# OLD_eps_bb1.net
KiCad netlist of a schematic drawn in Altium Designer
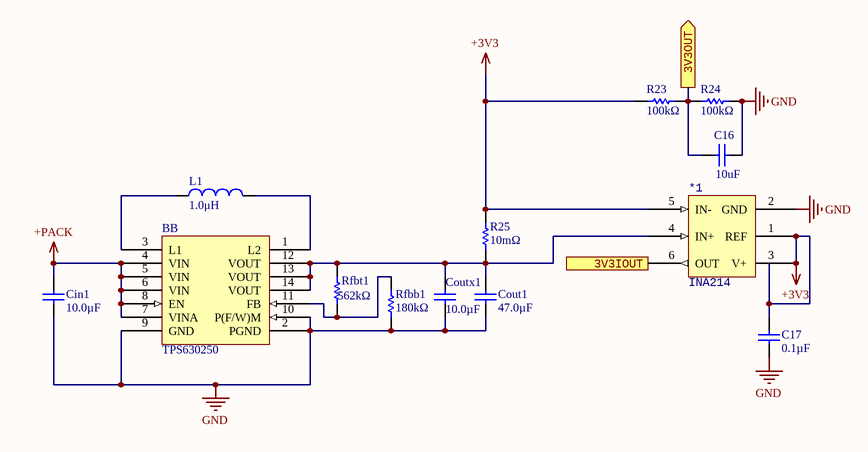
[diagram p0: OLD_eps_bb1.SchDoc]

(export (version "E")
  (design (tool "Eeschema 10.0.6"))
  (components
    (comp (ref "*1")
      (value "INA214")
      (footprint "SOT65P210X110-6N")
      (description "Current monitor")
      (libsource (lib "EPS") (part "INA214"))
    )
    (comp (ref "BB")
      (value "TPS630250")
      (footprint "RNC0014A")
      (description "Buck-boost converter")
      (libsource (lib "heron-general") (part "TPS630250"))
    )
    (comp (ref "C16")
      (value "10uF")
      (footprint "1608[0603]")
      (description "Capacitor")
      (fields (field (name "PUBLISHER") "Altium Limited"))
      (libsource (lib "Miscellaneous Devices") (part "Cap"))
    )
    (comp (ref "C17")
      (value "0.1µF")
      (footprint "1608[0603]")
      (description "Capacitor (Semiconductor SIM Model)")
      (fields (field (name "PUBLISHER") "Altium Limited"))
      (libsource (lib "Miscellaneous Devices") (part "Cap Semi"))
    )
    (comp (ref "Cin1")
      (value "10.0µF")
      (footprint "1608[0603]")
      (description "Capacitor")
      (fields (field (name "PUBLISHER") "Altium Limited"))
      (libsource (lib "Miscellaneous Devices") (part "Cap"))
    )
    (comp (ref "Cout1")
      (value "47.0µF")
      (footprint "1608[0603]")
      (description "Capacitor")
      (fields (field (name "PUBLISHER") "Altium Limited"))
      (libsource (lib "Miscellaneous Devices") (part "Cap"))
    )
    (comp (ref "Coutx1")
      (value "10.0µF")
      (footprint "1608[0603]")
      (description "Capacitor")
      (fields (field (name "PUBLISHER") "Altium Limited"))
      (libsource (lib "Miscellaneous Devices") (part "Cap"))
    )
    (comp (ref "L1")
      (value "1.0μH")
      (footprint "1608[0603]")
      (description "Inductor")
      (fields (field (name "PUBLISHER") "Altium Limited"))
      (libsource (lib "Miscellaneous Devices") (part "Inductor"))
    )
    (comp (ref "R23")
      (value "100kΩ")
      (footprint "1608[0603]")
      (description "Resistor")
      (fields (field (name "PUBLISHER") "Altium Limited"))
      (libsource (lib "Miscellaneous Devices") (part "Res1"))
    )
    (comp (ref "R24")
      (value "100kΩ")
      (footprint "1608[0603]")
      (description "Resistor")
      (fields (field (name "PUBLISHER") "Altium Limited"))
      (libsource (lib "Miscellaneous Devices") (part "Res1"))
    )
    (comp (ref "R25")
      (value "10mΩ")
      (footprint "1608[0603]")
      (description "Resistor")
      (fields (field (name "PUBLISHER") "Altium Limited"))
      (libsource (lib "Miscellaneous Devices") (part "Res1"))
    )
    (comp (ref "Rfbb1")
      (value "180kΩ")
      (footprint "1608[0603]")
      (description "Resistor")
      (fields (field (name "PUBLISHER") "Altium Limited"))
      (libsource (lib "Miscellaneous Devices") (part "Res1"))
    )
    (comp (ref "Rfbt1")
      (value "562kΩ")
      (footprint "1608[0603]")
      (description "Resistor")
      (fields (field (name "PUBLISHER") "Altium Limited"))
      (libsource (lib "Miscellaneous Devices") (part "Res1"))
    )
  )
  (nets
    (net (code "1") (name "+3V3") (class "Default")
      (node (ref "*1") (pin "1") (pinfunction "REF_1") (pintype "passive"))
      (node (ref "*1") (pin "3") (pinfunction "V+_3") (pintype "power_in"))
      (node (ref "*1") (pin "5") (pinfunction "IN-_5") (pintype "input"))
      (node (ref "C17") (pin "2") (pinfunction "2_2") (pintype "passive"))
      (node (ref "R23") (pin "1") (pinfunction "1_1") (pintype "passive"))
      (node (ref "R25") (pin "2") (pinfunction "2_2") (pintype "passive"))
    )
    (net (code "2") (name "+PACK") (class "Default")
      (node (ref "BB") (pin "4") (pinfunction "VIN_4") (pintype "power_in"))
      (node (ref "BB") (pin "5") (pinfunction "VIN_5") (pintype "power_in"))
      (node (ref "BB") (pin "6") (pinfunction "VIN_6") (pintype "power_in"))
      (node (ref "BB") (pin "7") (pinfunction "VINA_7") (pintype "power_in"))
      (node (ref "BB") (pin "8") (pinfunction "EN_8") (pintype "input"))
      (node (ref "Cin1") (pin "2") (pinfunction "2_2") (pintype "passive"))
    )
    (net (code "3") (name "/3V3IOUT") (class "Default")
      (node (ref "*1") (pin "6") (pinfunction "OUT_6") (pintype "output"))
    )
    (net (code "4") (name "/3V3OUT") (class "Default")
      (node (ref "C16") (pin "2") (pinfunction "2_2") (pintype "passive"))
      (node (ref "R23") (pin "2") (pinfunction "2_2") (pintype "passive"))
      (node (ref "R24") (pin "1") (pinfunction "1_1") (pintype "passive"))
    )
    (net (code "5") (name "GND") (class "Default")
      (node (ref "*1") (pin "2") (pinfunction "GND_2") (pintype "power_in"))
      (node (ref "BB") (pin "10") (pinfunction "P(F/W)M_10") (pintype "input"))
      (node (ref "BB") (pin "2") (pinfunction "PGND_2") (pintype "power_in"))
      (node (ref "BB") (pin "9") (pinfunction "GND_9") (pintype "power_in"))
      (node (ref "C16") (pin "1") (pinfunction "1_1") (pintype "passive"))
      (node (ref "C17") (pin "1") (pinfunction "1_1") (pintype "passive"))
      (node (ref "Cin1") (pin "1") (pinfunction "1_1") (pintype "passive"))
      (node (ref "Cout1") (pin "1") (pinfunction "1_1") (pintype "passive"))
      (node (ref "Coutx1") (pin "1") (pinfunction "1_1") (pintype "passive"))
      (node (ref "R24") (pin "2") (pinfunction "2_2") (pintype "passive"))
      (node (ref "Rfbb1") (pin "1") (pinfunction "1_1") (pintype "passive"))
    )
    (net (code "6") (name "Net-(*1-IN+)") (class "Default")
      (node (ref "*1") (pin "4") (pinfunction "IN+_4") (pintype "input"))
      (node (ref "BB") (pin "12") (pinfunction "VOUT_12") (pintype "passive"))
      (node (ref "BB") (pin "13") (pinfunction "VOUT_13") (pintype "passive"))
      (node (ref "BB") (pin "14") (pinfunction "VOUT_14") (pintype "passive"))
      (node (ref "Cout1") (pin "2") (pinfunction "2_2") (pintype "passive"))
      (node (ref "Coutx1") (pin "2") (pinfunction "2_2") (pintype "passive"))
      (node (ref "R25") (pin "1") (pinfunction "1_1") (pintype "passive"))
      (node (ref "Rfbt1") (pin "1") (pinfunction "1_1") (pintype "passive"))
    )
    (net (code "7") (name "Net-(BB-FB)") (class "Default")
      (node (ref "BB") (pin "11") (pinfunction "FB_11") (pintype "input"))
      (node (ref "Rfbb1") (pin "2") (pinfunction "2_2") (pintype "passive"))
      (node (ref "Rfbt1") (pin "2") (pinfunction "2_2") (pintype "passive"))
    )
    (net (code "8") (name "Net-(BB-L1)") (class "Default")
      (node (ref "BB") (pin "3") (pinfunction "L1_3") (pintype "power_in"))
      (node (ref "L1") (pin "1") (pinfunction "1_1") (pintype "passive"))
    )
    (net (code "9") (name "Net-(BB-L2)") (class "Default")
      (node (ref "BB") (pin "1") (pinfunction "L2_1") (pintype "power_in"))
      (node (ref "L1") (pin "2") (pinfunction "2_2") (pintype "passive"))
    )
  )
)
